# lcd20x4_left.net
KiCad netlist of a schematic drawn in EAGLE
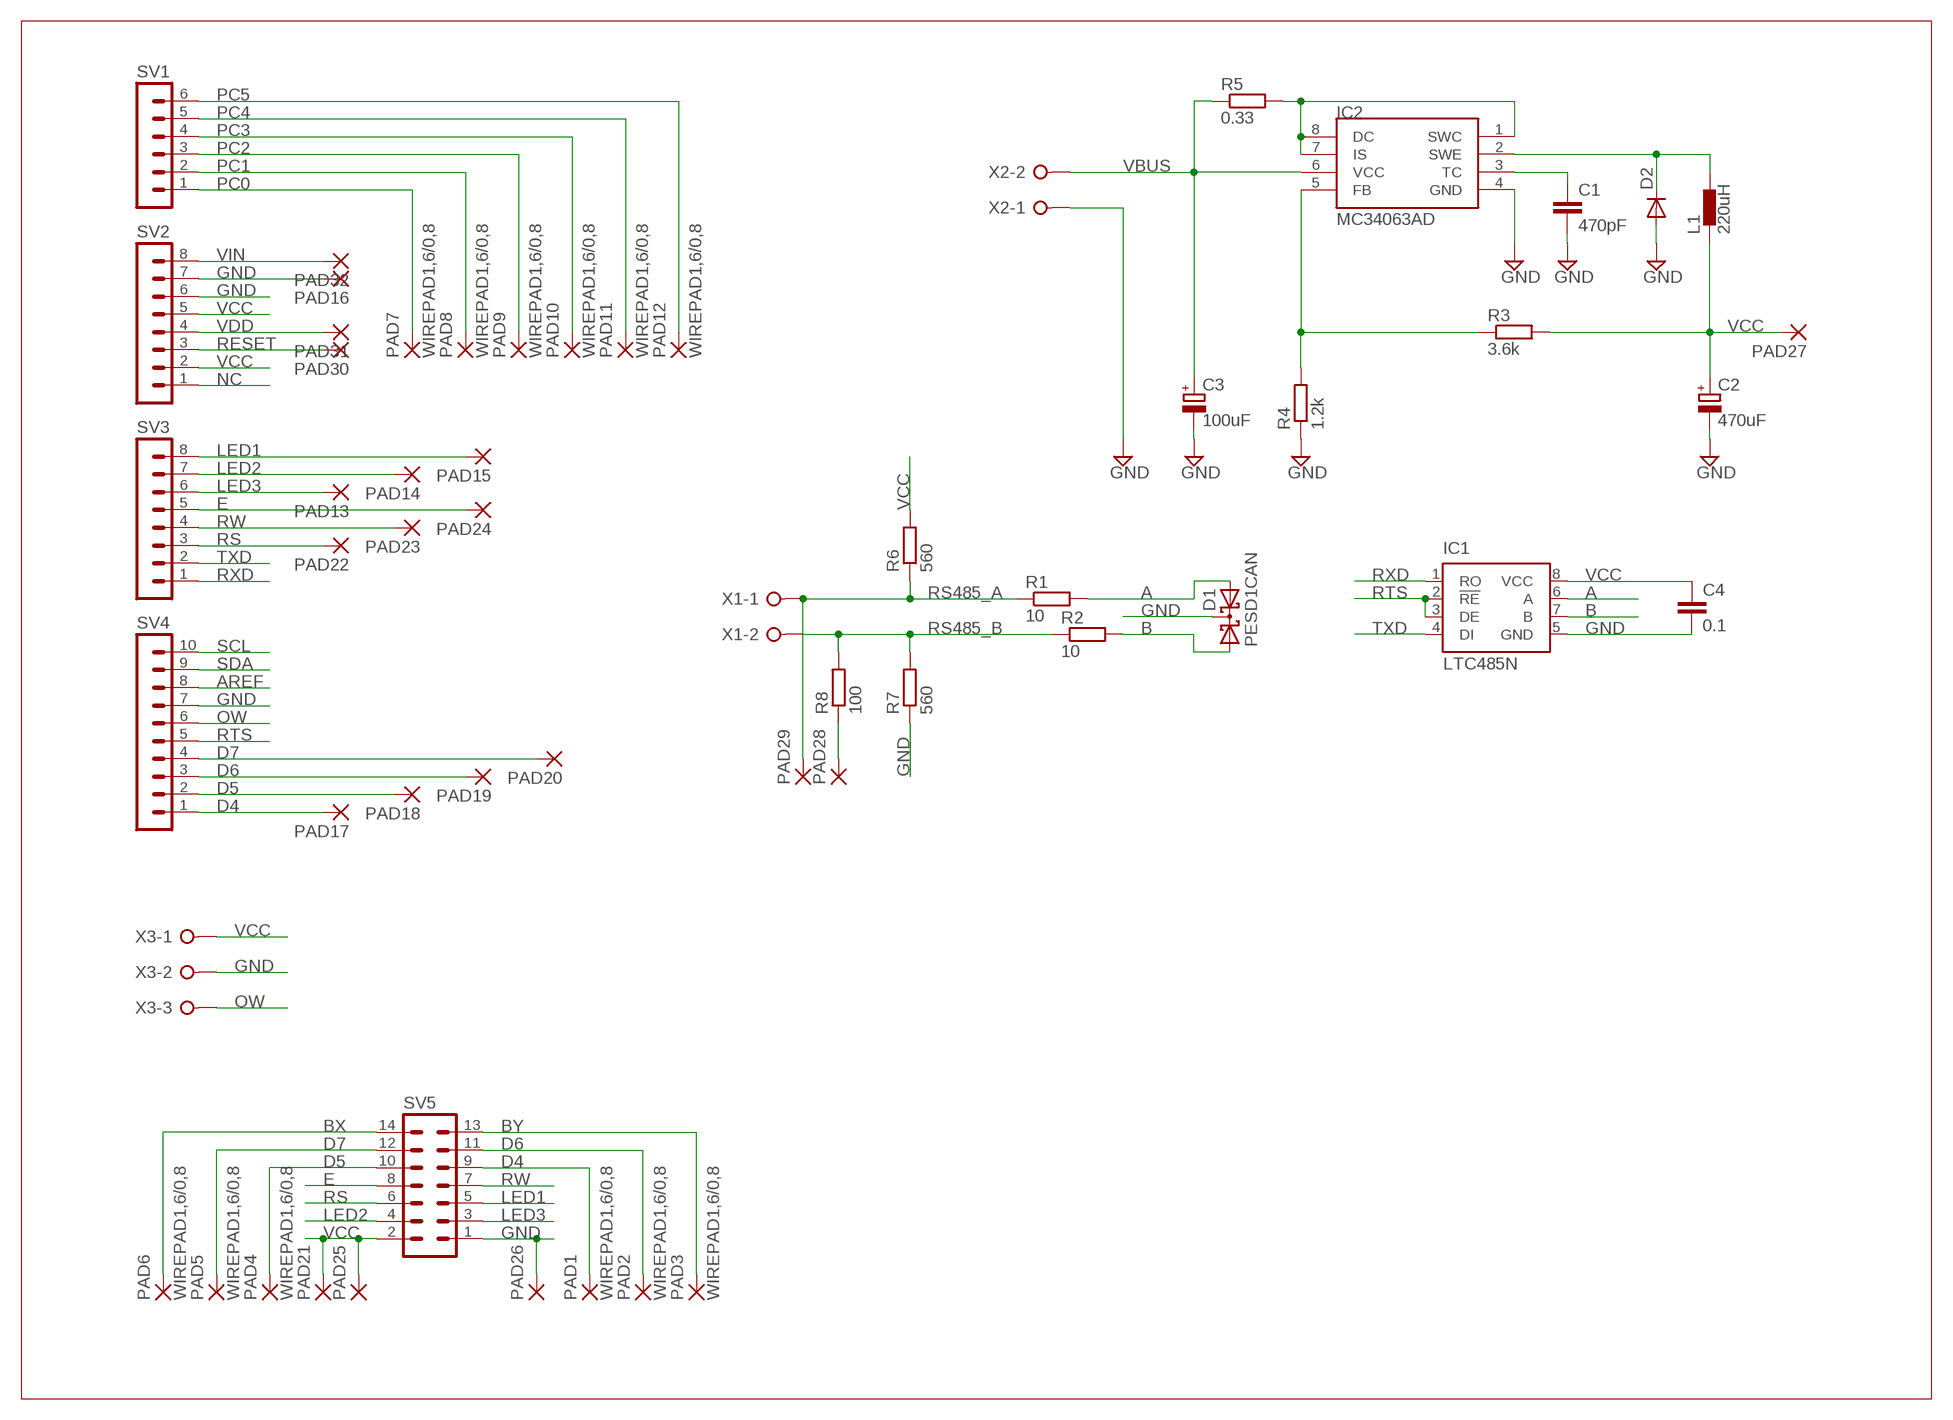
[diagram p0: schematic, sheet 1]

(export (version "E")
  (design (tool "Eeschema 10.0.6"))
  (components
    (comp (ref "C1")
      (value "470pF")
      (footprint "eagle-import:C0805")
      (libsource (lib "eagle-import") (part "C-EUC0805"))
    )
    (comp (ref "C2")
      (value "470uF")
      (footprint "eagle-import:E3,5-8")
      (libsource (lib "eagle-import") (part "CPOL-EUE3.5-8"))
    )
    (comp (ref "C3")
      (value "100uF")
      (footprint "eagle-import:E3,5-8")
      (libsource (lib "eagle-import") (part "CPOL-EUE3.5-8"))
    )
    (comp (ref "C4")
      (value "0.1")
      (footprint "eagle-import:C0805")
      (libsource (lib "eagle-import") (part "C-EUC0805"))
    )
    (comp (ref "D1")
      (value "PESD1CAN")
      (footprint "eagle-import:SOT23")
      (libsource (lib "eagle-import") (part "BAT54C"))
    )
    (comp (ref "D2")
      (value "DIODE-SMB")
      (footprint "eagle-import:SMB")
      (libsource (lib "eagle-import") (part "DIODE-SMB"))
    )
    (comp (ref "IC1")
      (value "LTC485N")
      (footprint "eagle-import:DIL08")
      (libsource (lib "eagle-import") (part "LTC485N"))
    )
    (comp (ref "IC2")
      (value "MC34063AD")
      (footprint "eagle-import:SOIC8")
      (libsource (lib "eagle-import") (part "MC34063AD"))
    )
    (comp (ref "L1")
      (value "220uH")
      (footprint "eagle-import:DR1030")
      (libsource (lib "eagle-import") (part "DR1030"))
    )
    (comp (ref "PAD1")
      (value "WIREPAD1,6/0,8")
      (footprint "eagle-import:1,6_0,8")
      (libsource (lib "eagle-import") (part "WIREPAD1,6/0,8"))
    )
    (comp (ref "PAD2")
      (value "WIREPAD1,6/0,8")
      (footprint "eagle-import:1,6_0,8")
      (libsource (lib "eagle-import") (part "WIREPAD1,6/0,8"))
    )
    (comp (ref "PAD3")
      (value "WIREPAD1,6/0,8")
      (footprint "eagle-import:1,6_0,8")
      (libsource (lib "eagle-import") (part "WIREPAD1,6/0,8"))
    )
    (comp (ref "PAD4")
      (value "WIREPAD1,6/0,8")
      (footprint "eagle-import:1,6_0,8")
      (libsource (lib "eagle-import") (part "WIREPAD1,6/0,8"))
    )
    (comp (ref "PAD5")
      (value "WIREPAD1,6/0,8")
      (footprint "eagle-import:1,6_0,8")
      (libsource (lib "eagle-import") (part "WIREPAD1,6/0,8"))
    )
    (comp (ref "PAD6")
      (value "WIREPAD1,6/0,8")
      (footprint "eagle-import:1,6_0,8")
      (libsource (lib "eagle-import") (part "WIREPAD1,6/0,8"))
    )
    (comp (ref "PAD7")
      (value "WIREPAD1,6/0,8")
      (footprint "eagle-import:1,6_0,8")
      (libsource (lib "eagle-import") (part "WIREPAD1,6/0,8"))
    )
    (comp (ref "PAD8")
      (value "WIREPAD1,6/0,8")
      (footprint "eagle-import:1,6_0,8")
      (libsource (lib "eagle-import") (part "WIREPAD1,6/0,8"))
    )
    (comp (ref "PAD9")
      (value "WIREPAD1,6/0,8")
      (footprint "eagle-import:1,6_0,8")
      (libsource (lib "eagle-import") (part "WIREPAD1,6/0,8"))
    )
    (comp (ref "PAD10")
      (value "WIREPAD1,6/0,8")
      (footprint "eagle-import:1,6_0,8")
      (libsource (lib "eagle-import") (part "WIREPAD1,6/0,8"))
    )
    (comp (ref "PAD11")
      (value "WIREPAD1,6/0,8")
      (footprint "eagle-import:1,6_0,8")
      (libsource (lib "eagle-import") (part "WIREPAD1,6/0,8"))
    )
    (comp (ref "PAD12")
      (value "WIREPAD1,6/0,8")
      (footprint "eagle-import:1,6_0,8")
      (libsource (lib "eagle-import") (part "WIREPAD1,6/0,8"))
    )
    (comp (ref "PAD13")
      (value "WIREPAD1,6/0,8")
      (footprint "eagle-import:1,6_0,8")
      (libsource (lib "eagle-import") (part "WIREPAD1,6/0,8"))
    )
    (comp (ref "PAD14")
      (value "WIREPAD1,6/0,8")
      (footprint "eagle-import:1,6_0,8")
      (libsource (lib "eagle-import") (part "WIREPAD1,6/0,8"))
    )
    (comp (ref "PAD15")
      (value "WIREPAD1,6/0,8")
      (footprint "eagle-import:1,6_0,8")
      (libsource (lib "eagle-import") (part "WIREPAD1,6/0,8"))
    )
    (comp (ref "PAD16")
      (value "WIREPAD1,6/0,8")
      (footprint "eagle-import:1,6_0,8")
      (libsource (lib "eagle-import") (part "WIREPAD1,6/0,8"))
    )
    (comp (ref "PAD17")
      (value "WIREPAD1,6/0,8")
      (footprint "eagle-import:1,6_0,8")
      (libsource (lib "eagle-import") (part "WIREPAD1,6/0,8"))
    )
    (comp (ref "PAD18")
      (value "WIREPAD1,6/0,8")
      (footprint "eagle-import:1,6_0,8")
      (libsource (lib "eagle-import") (part "WIREPAD1,6/0,8"))
    )
    (comp (ref "PAD19")
      (value "WIREPAD1,6/0,8")
      (footprint "eagle-import:1,6_0,8")
      (libsource (lib "eagle-import") (part "WIREPAD1,6/0,8"))
    )
    (comp (ref "PAD20")
      (value "WIREPAD1,6/0,8")
      (footprint "eagle-import:1,6_0,8")
      (libsource (lib "eagle-import") (part "WIREPAD1,6/0,8"))
    )
    (comp (ref "PAD21")
      (value "WIREPAD1,6/0,8")
      (footprint "eagle-import:1,6_0,8")
      (libsource (lib "eagle-import") (part "WIREPAD1,6/0,8"))
    )
    (comp (ref "PAD22")
      (value "WIREPAD1,6/0,8")
      (footprint "eagle-import:1,6_0,8")
      (libsource (lib "eagle-import") (part "WIREPAD1,6/0,8"))
    )
    (comp (ref "PAD23")
      (value "WIREPAD1,6/0,8")
      (footprint "eagle-import:1,6_0,8")
      (libsource (lib "eagle-import") (part "WIREPAD1,6/0,8"))
    )
    (comp (ref "PAD24")
      (value "WIREPAD1,6/0,8")
      (footprint "eagle-import:1,6_0,8")
      (libsource (lib "eagle-import") (part "WIREPAD1,6/0,8"))
    )
    (comp (ref "PAD25")
      (value "WIREPAD1,6/0,8")
      (footprint "eagle-import:1,6_0,8")
      (libsource (lib "eagle-import") (part "WIREPAD1,6/0,8"))
    )
    (comp (ref "PAD26")
      (value "WIREPAD1,6/0,8")
      (footprint "eagle-import:1,6_0,8")
      (libsource (lib "eagle-import") (part "WIREPAD1,6/0,8"))
    )
    (comp (ref "PAD27")
      (value "WIREPAD1,6/0,8")
      (footprint "eagle-import:1,6_0,8")
      (libsource (lib "eagle-import") (part "WIREPAD1,6/0,8"))
    )
    (comp (ref "PAD28")
      (value "WIREPAD1,6/0,8")
      (footprint "eagle-import:1,6_0,8")
      (libsource (lib "eagle-import") (part "WIREPAD1,6/0,8"))
    )
    (comp (ref "PAD29")
      (value "WIREPAD1,6/0,8")
      (footprint "eagle-import:1,6_0,8")
      (libsource (lib "eagle-import") (part "WIREPAD1,6/0,8"))
    )
    (comp (ref "PAD30")
      (value "WIREPAD1,6/0,8")
      (footprint "eagle-import:1,6_0,8")
      (libsource (lib "eagle-import") (part "WIREPAD1,6/0,8"))
    )
    (comp (ref "PAD31")
      (value "WIREPAD1,6/0,8")
      (footprint "eagle-import:1,6_0,8")
      (libsource (lib "eagle-import") (part "WIREPAD1,6/0,8"))
    )
    (comp (ref "PAD32")
      (value "WIREPAD1,6/0,8")
      (footprint "eagle-import:1,6_0,8")
      (libsource (lib "eagle-import") (part "WIREPAD1,6/0,8"))
    )
    (comp (ref "R1")
      (value "10")
      (footprint "eagle-import:0207_10")
      (libsource (lib "eagle-import") (part "R-EU_0207/10"))
    )
    (comp (ref "R2")
      (value "10")
      (footprint "eagle-import:0207_10")
      (libsource (lib "eagle-import") (part "R-EU_0207/10"))
    )
    (comp (ref "R3")
      (value "3.6k")
      (footprint "eagle-import:R0805")
      (libsource (lib "eagle-import") (part "R-EU_R0805"))
    )
    (comp (ref "R4")
      (value "1.2k")
      (footprint "eagle-import:R0805")
      (libsource (lib "eagle-import") (part "R-EU_R0805"))
    )
    (comp (ref "R5")
      (value "0.33")
      (footprint "eagle-import:M1206")
      (libsource (lib "eagle-import") (part "R-EU_M1206"))
    )
    (comp (ref "R6")
      (value "560")
      (footprint "eagle-import:0207_10")
      (libsource (lib "eagle-import") (part "R-EU_0207/10"))
    )
    (comp (ref "R7")
      (value "560")
      (footprint "eagle-import:0207_10")
      (libsource (lib "eagle-import") (part "R-EU_0207/10"))
    )
    (comp (ref "R8")
      (value "100")
      (footprint "eagle-import:0207_10")
      (libsource (lib "eagle-import") (part "R-EU_0207/10"))
    )
    (comp (ref "SV1")
      (value "MA06-1")
      (footprint "eagle-import:MA06-1")
      (libsource (lib "eagle-import") (part "MA06-1"))
    )
    (comp (ref "SV2")
      (value "MA08-1")
      (footprint "eagle-import:MA08-1")
      (libsource (lib "eagle-import") (part "MA08-1"))
    )
    (comp (ref "SV3")
      (value "MA08-1")
      (footprint "eagle-import:MA08-1")
      (libsource (lib "eagle-import") (part "MA08-1"))
    )
    (comp (ref "SV4")
      (value "MA10-1")
      (footprint "eagle-import:MA10-1")
      (libsource (lib "eagle-import") (part "MA10-1"))
    )
    (comp (ref "SV5")
      (value "MA07-2")
      (footprint "eagle-import:MA07-2")
      (libsource (lib "eagle-import") (part "MA07-2"))
    )
    (comp (ref "X1")
      (value "W237-02P")
      (footprint "eagle-import:W237-132")
      (libsource (lib "eagle-import") (part "W237-02P"))
    )
    (comp (ref "X2")
      (value "W237-02P")
      (footprint "eagle-import:W237-132")
      (libsource (lib "eagle-import") (part "W237-02P"))
    )
    (comp (ref "X3")
      (value "W237-03P")
      (footprint "eagle-import:W237-133")
      (libsource (lib "eagle-import") (part "W237-03P"))
    )
  )
  (nets
    (net (code "1") (name "/A") (class "Default")
      (node (ref "D1") (pin "2") (pinfunction "A2_2") (pintype "passive"))
      (node (ref "IC1") (pin "6") (pinfunction "A_6") (pintype "bidirectional"))
      (node (ref "R1") (pin "2") (pinfunction "2_2") (pintype "passive"))
    )
    (net (code "2") (name "/AREF") (class "Default")
      (node (ref "SV4") (pin "8") (pinfunction "8_8") (pintype "passive"))
    )
    (net (code "3") (name "/B") (class "Default")
      (node (ref "D1") (pin "1") (pinfunction "A1_1") (pintype "passive"))
      (node (ref "IC1") (pin "7") (pinfunction "B_7") (pintype "bidirectional"))
      (node (ref "R2") (pin "2") (pinfunction "2_2") (pintype "passive"))
    )
    (net (code "4") (name "/BX") (class "Default")
      (node (ref "PAD6") (pin "1") (pinfunction "P_1") (pintype "passive"))
      (node (ref "SV5") (pin "14") (pinfunction "14_14") (pintype "passive"))
    )
    (net (code "5") (name "/BY") (class "Default")
      (node (ref "PAD3") (pin "1") (pinfunction "P_1") (pintype "passive"))
      (node (ref "SV5") (pin "13") (pinfunction "13_13") (pintype "passive"))
    )
    (net (code "6") (name "/D4") (class "Default")
      (node (ref "PAD1") (pin "1") (pinfunction "P_1") (pintype "passive"))
      (node (ref "PAD17") (pin "1") (pinfunction "P_1") (pintype "passive"))
      (node (ref "SV4") (pin "1") (pinfunction "1_1") (pintype "passive"))
      (node (ref "SV5") (pin "9") (pinfunction "9_9") (pintype "passive"))
    )
    (net (code "7") (name "/D5") (class "Default")
      (node (ref "PAD18") (pin "1") (pinfunction "P_1") (pintype "passive"))
      (node (ref "PAD4") (pin "1") (pinfunction "P_1") (pintype "passive"))
      (node (ref "SV4") (pin "2") (pinfunction "2_2") (pintype "passive"))
      (node (ref "SV5") (pin "10") (pinfunction "10_10") (pintype "passive"))
    )
    (net (code "8") (name "/D6") (class "Default")
      (node (ref "PAD19") (pin "1") (pinfunction "P_1") (pintype "passive"))
      (node (ref "PAD2") (pin "1") (pinfunction "P_1") (pintype "passive"))
      (node (ref "SV4") (pin "3") (pinfunction "3_3") (pintype "passive"))
      (node (ref "SV5") (pin "11") (pinfunction "11_11") (pintype "passive"))
    )
    (net (code "9") (name "/D7") (class "Default")
      (node (ref "PAD20") (pin "1") (pinfunction "P_1") (pintype "passive"))
      (node (ref "PAD5") (pin "1") (pinfunction "P_1") (pintype "passive"))
      (node (ref "SV4") (pin "4") (pinfunction "4_4") (pintype "passive"))
      (node (ref "SV5") (pin "12") (pinfunction "12_12") (pintype "passive"))
    )
    (net (code "10") (name "/E") (class "Default")
      (node (ref "PAD24") (pin "1") (pinfunction "P_1") (pintype "passive"))
      (node (ref "SV3") (pin "5") (pinfunction "5_5") (pintype "passive"))
      (node (ref "SV5") (pin "8") (pinfunction "8_8") (pintype "passive"))
    )
    (net (code "11") (name "/LED1") (class "Default")
      (node (ref "PAD15") (pin "1") (pinfunction "P_1") (pintype "passive"))
      (node (ref "SV3") (pin "8") (pinfunction "8_8") (pintype "passive"))
      (node (ref "SV5") (pin "5") (pinfunction "5_5") (pintype "passive"))
    )
    (net (code "12") (name "/LED2") (class "Default")
      (node (ref "PAD14") (pin "1") (pinfunction "P_1") (pintype "passive"))
      (node (ref "SV3") (pin "7") (pinfunction "7_7") (pintype "passive"))
      (node (ref "SV5") (pin "4") (pinfunction "4_4") (pintype "passive"))
    )
    (net (code "13") (name "/LED3") (class "Default")
      (node (ref "PAD13") (pin "1") (pinfunction "P_1") (pintype "passive"))
      (node (ref "SV3") (pin "6") (pinfunction "6_6") (pintype "passive"))
      (node (ref "SV5") (pin "3") (pinfunction "3_3") (pintype "passive"))
    )
    (net (code "14") (name "/NC") (class "Default")
      (node (ref "SV2") (pin "1") (pinfunction "1_1") (pintype "passive"))
    )
    (net (code "15") (name "/OW") (class "Default")
      (node (ref "SV4") (pin "6") (pinfunction "6_6") (pintype "passive"))
      (node (ref "X3") (pin "3") (pinfunction "KL_3") (pintype "passive"))
    )
    (net (code "16") (name "/PC0") (class "Default")
      (node (ref "PAD7") (pin "1") (pinfunction "P_1") (pintype "passive"))
      (node (ref "SV1") (pin "1") (pinfunction "1_1") (pintype "passive"))
    )
    (net (code "17") (name "/PC1") (class "Default")
      (node (ref "PAD8") (pin "1") (pinfunction "P_1") (pintype "passive"))
      (node (ref "SV1") (pin "2") (pinfunction "2_2") (pintype "passive"))
    )
    (net (code "18") (name "/PC2") (class "Default")
      (node (ref "PAD9") (pin "1") (pinfunction "P_1") (pintype "passive"))
      (node (ref "SV1") (pin "3") (pinfunction "3_3") (pintype "passive"))
    )
    (net (code "19") (name "/PC3") (class "Default")
      (node (ref "PAD10") (pin "1") (pinfunction "P_1") (pintype "passive"))
      (node (ref "SV1") (pin "4") (pinfunction "4_4") (pintype "passive"))
    )
    (net (code "20") (name "/PC4") (class "Default")
      (node (ref "PAD11") (pin "1") (pinfunction "P_1") (pintype "passive"))
      (node (ref "SV1") (pin "5") (pinfunction "5_5") (pintype "passive"))
    )
    (net (code "21") (name "/PC5") (class "Default")
      (node (ref "PAD12") (pin "1") (pinfunction "P_1") (pintype "passive"))
      (node (ref "SV1") (pin "6") (pinfunction "6_6") (pintype "passive"))
    )
    (net (code "22") (name "/RESET") (class "Default")
      (node (ref "PAD30") (pin "1") (pinfunction "P_1") (pintype "passive"))
      (node (ref "SV2") (pin "3") (pinfunction "3_3") (pintype "passive"))
    )
    (net (code "23") (name "/RS") (class "Default")
      (node (ref "PAD22") (pin "1") (pinfunction "P_1") (pintype "passive"))
      (node (ref "SV3") (pin "3") (pinfunction "3_3") (pintype "passive"))
      (node (ref "SV5") (pin "6") (pinfunction "6_6") (pintype "passive"))
    )
    (net (code "24") (name "/RS485_A") (class "Default")
      (node (ref "PAD29") (pin "1") (pinfunction "P_1") (pintype "passive"))
      (node (ref "R1") (pin "1") (pinfunction "1_1") (pintype "passive"))
      (node (ref "R6") (pin "1") (pinfunction "1_1") (pintype "passive"))
      (node (ref "X1") (pin "1") (pinfunction "KL_1") (pintype "passive"))
    )
    (net (code "25") (name "/RS485_B") (class "Default")
      (node (ref "R2") (pin "1") (pinfunction "1_1") (pintype "passive"))
      (node (ref "R7") (pin "2") (pinfunction "2_2") (pintype "passive"))
      (node (ref "R8") (pin "2") (pinfunction "2_2") (pintype "passive"))
      (node (ref "X1") (pin "2") (pinfunction "KL_2") (pintype "passive"))
    )
    (net (code "26") (name "/RTS") (class "Default")
      (node (ref "IC1") (pin "2") (pinfunction "~{RE}_2") (pintype "input"))
      (node (ref "IC1") (pin "3") (pinfunction "DE_3") (pintype "input"))
      (node (ref "SV4") (pin "5") (pinfunction "5_5") (pintype "passive"))
    )
    (net (code "27") (name "/RW") (class "Default")
      (node (ref "PAD23") (pin "1") (pinfunction "P_1") (pintype "passive"))
      (node (ref "SV3") (pin "4") (pinfunction "4_4") (pintype "passive"))
      (node (ref "SV5") (pin "7") (pinfunction "7_7") (pintype "passive"))
    )
    (net (code "28") (name "/RXD") (class "Default")
      (node (ref "IC1") (pin "1") (pinfunction "RO_1") (pintype "output"))
      (node (ref "SV3") (pin "1") (pinfunction "1_1") (pintype "passive"))
    )
    (net (code "29") (name "/SCL") (class "Default")
      (node (ref "SV4") (pin "10") (pinfunction "10_10") (pintype "passive"))
    )
    (net (code "30") (name "/SDA") (class "Default")
      (node (ref "SV4") (pin "9") (pinfunction "9_9") (pintype "passive"))
    )
    (net (code "31") (name "/TXD") (class "Default")
      (node (ref "IC1") (pin "4") (pinfunction "DI_4") (pintype "input"))
      (node (ref "SV3") (pin "2") (pinfunction "2_2") (pintype "passive"))
    )
    (net (code "32") (name "/VBUS") (class "Default")
      (node (ref "C3") (pin "+") (pinfunction "+_+") (pintype "passive"))
      (node (ref "IC2") (pin "6") (pinfunction "VCC_6") (pintype "passive"))
      (node (ref "R5") (pin "1") (pinfunction "1_1") (pintype "passive"))
      (node (ref "X2") (pin "2") (pinfunction "KL_2") (pintype "passive"))
    )
    (net (code "33") (name "/VCC") (class "Default")
      (node (ref "C2") (pin "+") (pinfunction "+_+") (pintype "passive"))
      (node (ref "C4") (pin "1") (pinfunction "1_1") (pintype "passive"))
      (node (ref "IC1") (pin "8") (pinfunction "VCC_8") (pintype "input"))
      (node (ref "L1") (pin "1") (pinfunction "1_1") (pintype "passive"))
      (node (ref "PAD21") (pin "1") (pinfunction "P_1") (pintype "passive"))
      (node (ref "PAD25") (pin "1") (pinfunction "P_1") (pintype "passive"))
      (node (ref "PAD27") (pin "1") (pinfunction "P_1") (pintype "passive"))
      (node (ref "R3") (pin "2") (pinfunction "2_2") (pintype "passive"))
      (node (ref "R6") (pin "2") (pinfunction "2_2") (pintype "passive"))
      (node (ref "SV2") (pin "2") (pinfunction "2_2") (pintype "passive"))
      (node (ref "SV2") (pin "5") (pinfunction "5_5") (pintype "passive"))
      (node (ref "SV5") (pin "2") (pinfunction "2_2") (pintype "passive"))
      (node (ref "X3") (pin "1") (pinfunction "KL_1") (pintype "passive"))
    )
    (net (code "34") (name "/VDD") (class "Default")
      (node (ref "PAD31") (pin "1") (pinfunction "P_1") (pintype "passive"))
      (node (ref "SV2") (pin "4") (pinfunction "4_4") (pintype "passive"))
    )
    (net (code "35") (name "/VIN") (class "Default")
      (node (ref "PAD32") (pin "1") (pinfunction "P_1") (pintype "passive"))
      (node (ref "SV2") (pin "8") (pinfunction "8_8") (pintype "passive"))
    )
    (net (code "36") (name "GND") (class "Default")
      (node (ref "C1") (pin "2") (pinfunction "2_2") (pintype "passive"))
      (node (ref "C2") (pin "-") (pinfunction "-_-") (pintype "passive"))
      (node (ref "C3") (pin "-") (pinfunction "-_-") (pintype "passive"))
      (node (ref "C4") (pin "2") (pinfunction "2_2") (pintype "passive"))
      (node (ref "D1") (pin "3") (pinfunction "CC_3") (pintype "passive"))
      (node (ref "D2") (pin "A") (pinfunction "A_A") (pintype "passive"))
      (node (ref "IC1") (pin "5") (pinfunction "GND_5") (pintype "input"))
      (node (ref "IC2") (pin "4") (pinfunction "GND_4") (pintype "passive"))
      (node (ref "PAD16") (pin "1") (pinfunction "P_1") (pintype "passive"))
      (node (ref "PAD26") (pin "1") (pinfunction "P_1") (pintype "passive"))
      (node (ref "R4") (pin "1") (pinfunction "1_1") (pintype "passive"))
      (node (ref "R7") (pin "1") (pinfunction "1_1") (pintype "passive"))
      (node (ref "SV2") (pin "6") (pinfunction "6_6") (pintype "passive"))
      (node (ref "SV2") (pin "7") (pinfunction "7_7") (pintype "passive"))
      (node (ref "SV4") (pin "7") (pinfunction "7_7") (pintype "passive"))
      (node (ref "SV5") (pin "1") (pinfunction "1_1") (pintype "passive"))
      (node (ref "X2") (pin "1") (pinfunction "KL_1") (pintype "passive"))
      (node (ref "X3") (pin "2") (pinfunction "KL_2") (pintype "passive"))
    )
    (net (code "37") (name "Net-(IC2-DC)") (class "Default")
      (node (ref "IC2") (pin "1") (pinfunction "SWC_1") (pintype "passive"))
      (node (ref "IC2") (pin "7") (pinfunction "IS_7") (pintype "passive"))
      (node (ref "IC2") (pin "8") (pinfunction "DC_8") (pintype "passive"))
      (node (ref "R5") (pin "2") (pinfunction "2_2") (pintype "passive"))
    )
    (net (code "38") (name "Net-(IC2-FB)") (class "Default")
      (node (ref "IC2") (pin "5") (pinfunction "FB_5") (pintype "passive"))
      (node (ref "R3") (pin "1") (pinfunction "1_1") (pintype "passive"))
      (node (ref "R4") (pin "2") (pinfunction "2_2") (pintype "passive"))
    )
    (net (code "39") (name "Net-(IC2-SWE)") (class "Default")
      (node (ref "D2") (pin "C") (pinfunction "C_C") (pintype "passive"))
      (node (ref "IC2") (pin "2") (pinfunction "SWE_2") (pintype "passive"))
      (node (ref "L1") (pin "2") (pinfunction "2_2") (pintype "passive"))
    )
    (net (code "40") (name "Net-(IC2-TC)") (class "Default")
      (node (ref "C1") (pin "1") (pinfunction "1_1") (pintype "passive"))
      (node (ref "IC2") (pin "3") (pinfunction "TC_3") (pintype "passive"))
    )
    (net (code "41") (name "Net-(PAD28-P)") (class "Default")
      (node (ref "PAD28") (pin "1") (pinfunction "P_1") (pintype "passive"))
      (node (ref "R8") (pin "1") (pinfunction "1_1") (pintype "passive"))
    )
  )
)
